# schematic.net
KiCad netlist of a schematic drawn in EAGLE
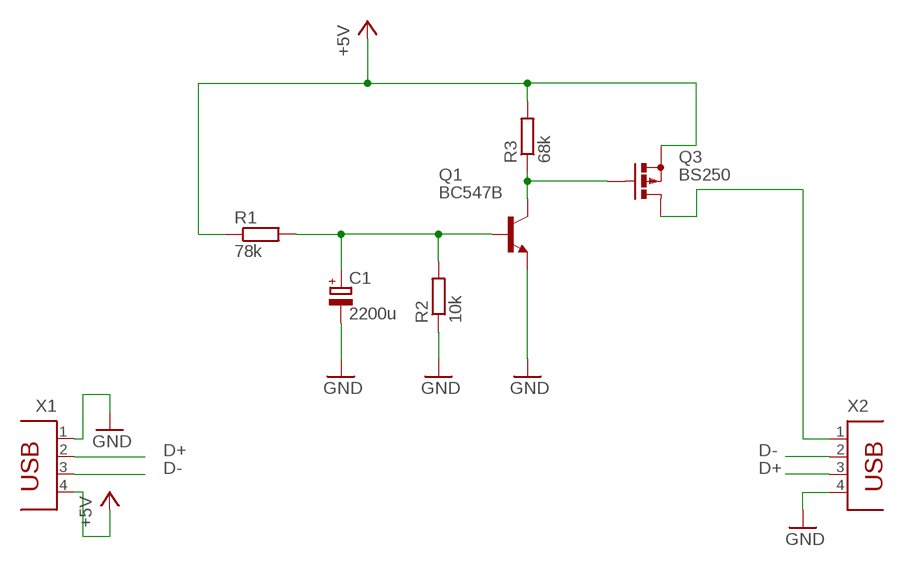
[diagram p0: schematic, sheet 1]

(export (version "E")
  (design (tool "Eeschema 10.0.6"))
  (components
    (comp (ref "C1")
      (value "2200u")
      (footprint "eagle-import:E3,5-8")
      (libsource (lib "eagle-import") (part "CPOL-EUE3.5-8"))
    )
    (comp (ref "Q1")
      (value "BC547B")
      (footprint "eagle-import:TO92")
      (libsource (lib "eagle-import") (part "BC547B"))
    )
    (comp (ref "Q3")
      (value "BS250")
      (footprint "eagle-import:SOT54E")
      (libsource (lib "eagle-import") (part "BS250"))
    )
    (comp (ref "R1")
      (value "78k")
      (footprint "eagle-import:0204_5")
      (libsource (lib "eagle-import") (part "R-EU_0204/5"))
    )
    (comp (ref "R2")
      (value "10k")
      (footprint "eagle-import:0204_5")
      (libsource (lib "eagle-import") (part "R-EU_0204/5"))
    )
    (comp (ref "R3")
      (value "68k")
      (footprint "eagle-import:0204_5")
      (libsource (lib "eagle-import") (part "R-EU_0204/5"))
    )
    (comp (ref "X1")
      (value "PN87520")
      (footprint "eagle-import:PN87520")
      (libsource (lib "eagle-import") (part "PN87520"))
    )
    (comp (ref "X2")
      (value "PN87520")
      (footprint "eagle-import:PN87520")
      (libsource (lib "eagle-import") (part "PN87520"))
    )
  )
  (nets
    (net (code "1") (name "+5V") (class "Default")
      (node (ref "Q3") (pin "S") (pinfunction "S_S") (pintype "passive"))
      (node (ref "R1") (pin "1") (pinfunction "1_1") (pintype "passive"))
      (node (ref "R3") (pin "2") (pinfunction "2_2") (pintype "passive"))
      (node (ref "X1") (pin "4") (pinfunction "4_4") (pintype "passive"))
    )
    (net (code "2") (name "/D+") (class "Default")
      (node (ref "X1") (pin "2") (pinfunction "2_2") (pintype "passive"))
      (node (ref "X2") (pin "3") (pinfunction "3_3") (pintype "passive"))
    )
    (net (code "3") (name "/D-") (class "Default")
      (node (ref "X1") (pin "3") (pinfunction "3_3") (pintype "passive"))
      (node (ref "X2") (pin "2") (pinfunction "2_2") (pintype "passive"))
    )
    (net (code "4") (name "GND") (class "Default")
      (node (ref "C1") (pin "-") (pinfunction "-_-") (pintype "passive"))
      (node (ref "Q1") (pin "1") (pinfunction "E_1") (pintype "passive"))
      (node (ref "R2") (pin "1") (pinfunction "1_1") (pintype "passive"))
      (node (ref "X1") (pin "1") (pinfunction "1_1") (pintype "passive"))
      (node (ref "X2") (pin "4") (pinfunction "4_4") (pintype "passive"))
    )
    (net (code "5") (name "Net-(Q1-B)") (class "Default")
      (node (ref "C1") (pin "+") (pinfunction "+_+") (pintype "passive"))
      (node (ref "Q1") (pin "2") (pinfunction "B_2") (pintype "passive"))
      (node (ref "R1") (pin "2") (pinfunction "2_2") (pintype "passive"))
      (node (ref "R2") (pin "2") (pinfunction "2_2") (pintype "passive"))
    )
    (net (code "6") (name "Net-(Q1-C)") (class "Default")
      (node (ref "Q1") (pin "3") (pinfunction "C_3") (pintype "passive"))
      (node (ref "Q3") (pin "G") (pinfunction "G_G") (pintype "passive"))
      (node (ref "R3") (pin "1") (pinfunction "1_1") (pintype "passive"))
    )
    (net (code "7") (name "Net-(Q3-PadD)") (class "Default")
      (node (ref "Q3") (pin "D") (pinfunction "D_D") (pintype "passive"))
      (node (ref "X2") (pin "1") (pinfunction "1_1") (pintype "passive"))
    )
  )
)
